# Sheet.net
KiCad netlist of a schematic drawn in Altium Designer
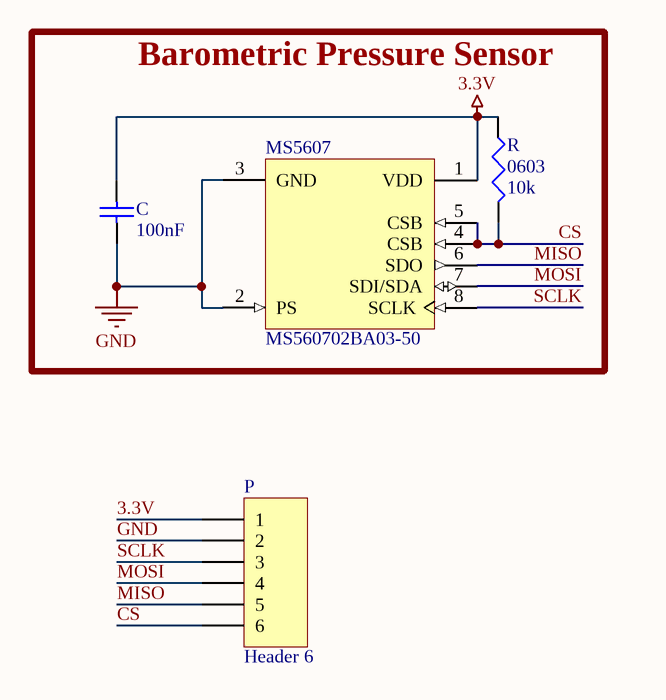
[diagram p0: Sheet.SchDoc]

(export (version "E")
  (design (tool "Eeschema 10.0.6"))
  (components
    (comp (ref "C")
      (value "100nF")
      (footprint "CAPC1608X95X40ML15T15")
      (fields (field (name "MANUFACTURER") "Vitramon") (field (name "PART NUMBER") "VJ0603Y104KXQCW1BC"))
      (libsource (lib "Altium Content Vault") (part "CAP"))
    )
    (comp (ref "MS5607")
      (value "MS560702BA03-50")
      (footprint "TECO-MS560702BA03-50_V")
      (fields (field (name "MANUFACTURER") "TE Connectivity"))
      (libsource (lib "Altium Content Vault") (part "TECO-MS560702BA03-8"))
    )
    (comp (ref "P")
      (value "Header 6")
      (footprint "HDR1X6")
      (description "Header, 6-Pin")
      (fields (field (name "PUBLISHER") "Altium Limited"))
      (libsource (lib "Miscellaneous Connectors") (part "Header 6"))
    )
    (comp (ref "R")
      (value "0603")
      (footprint "J1-0603")
      (description "Resistor")
      (fields (field (name "ALTIUM_VALUE") "10k") (field (name "PUBLISHER") "Altium Limited"))
      (libsource (lib "Miscellaneous Devices") (part "Res3"))
    )
  )
  (nets
    (net (code "1") (name "/CS") (class "Default")
      (node (ref "MS5607") (pin "4") (pinfunction "CSB_4") (pintype "input"))
      (node (ref "MS5607") (pin "5") (pinfunction "CSB_5") (pintype "input"))
      (node (ref "P") (pin "6") (pinfunction "6_6") (pintype "passive"))
      (node (ref "R") (pin "2") (pinfunction "2_2") (pintype "passive"))
    )
    (net (code "2") (name "/MISO") (class "Default")
      (node (ref "MS5607") (pin "6") (pinfunction "SDO_6") (pintype "output"))
      (node (ref "P") (pin "5") (pinfunction "5_5") (pintype "passive"))
    )
    (net (code "3") (name "/MOSI") (class "Default")
      (node (ref "MS5607") (pin "7") (pinfunction "SDI/SDA_7") (pintype "bidirectional"))
      (node (ref "P") (pin "4") (pinfunction "4_4") (pintype "passive"))
    )
    (net (code "4") (name "/SCLK") (class "Default")
      (node (ref "MS5607") (pin "8") (pinfunction "SCLK_8") (pintype "input"))
      (node (ref "P") (pin "3") (pinfunction "3_3") (pintype "passive"))
    )
    (net (code "5") (name "3.3V") (class "Default")
      (node (ref "C") (pin "2") (pinfunction "2_2") (pintype "passive"))
      (node (ref "MS5607") (pin "1") (pinfunction "VDD_1") (pintype "power_in"))
      (node (ref "P") (pin "1") (pinfunction "1_1") (pintype "passive"))
      (node (ref "R") (pin "1") (pinfunction "1_1") (pintype "passive"))
    )
    (net (code "6") (name "GND") (class "Default")
      (node (ref "C") (pin "1") (pinfunction "1_1") (pintype "passive"))
      (node (ref "MS5607") (pin "2") (pinfunction "PS_2") (pintype "input"))
      (node (ref "MS5607") (pin "3") (pinfunction "GND_3") (pintype "power_in"))
      (node (ref "P") (pin "2") (pinfunction "2_2") (pintype "passive"))
    )
  )
)
